# -.net
KiCad netlist of a schematic drawn in Altium Designer
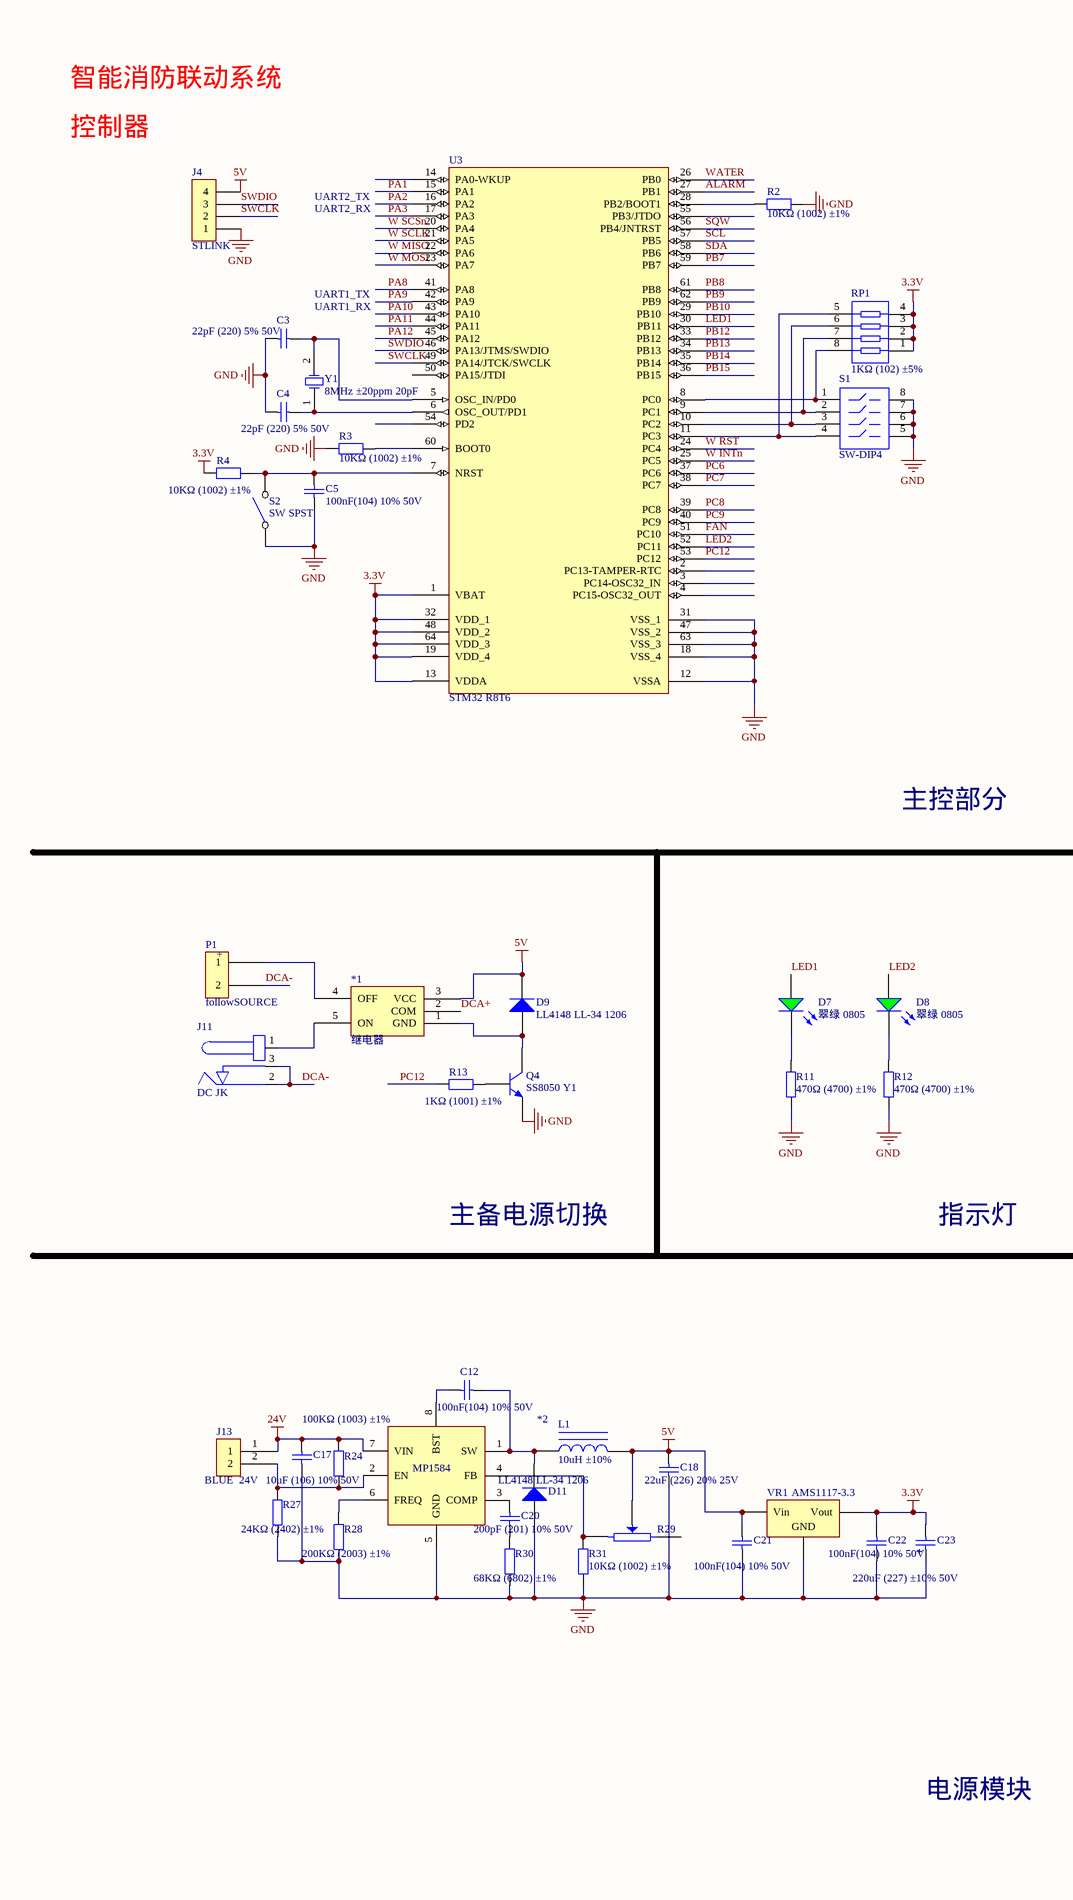
[diagram p0: 控制器最终图-论文用.SchDoc, left]
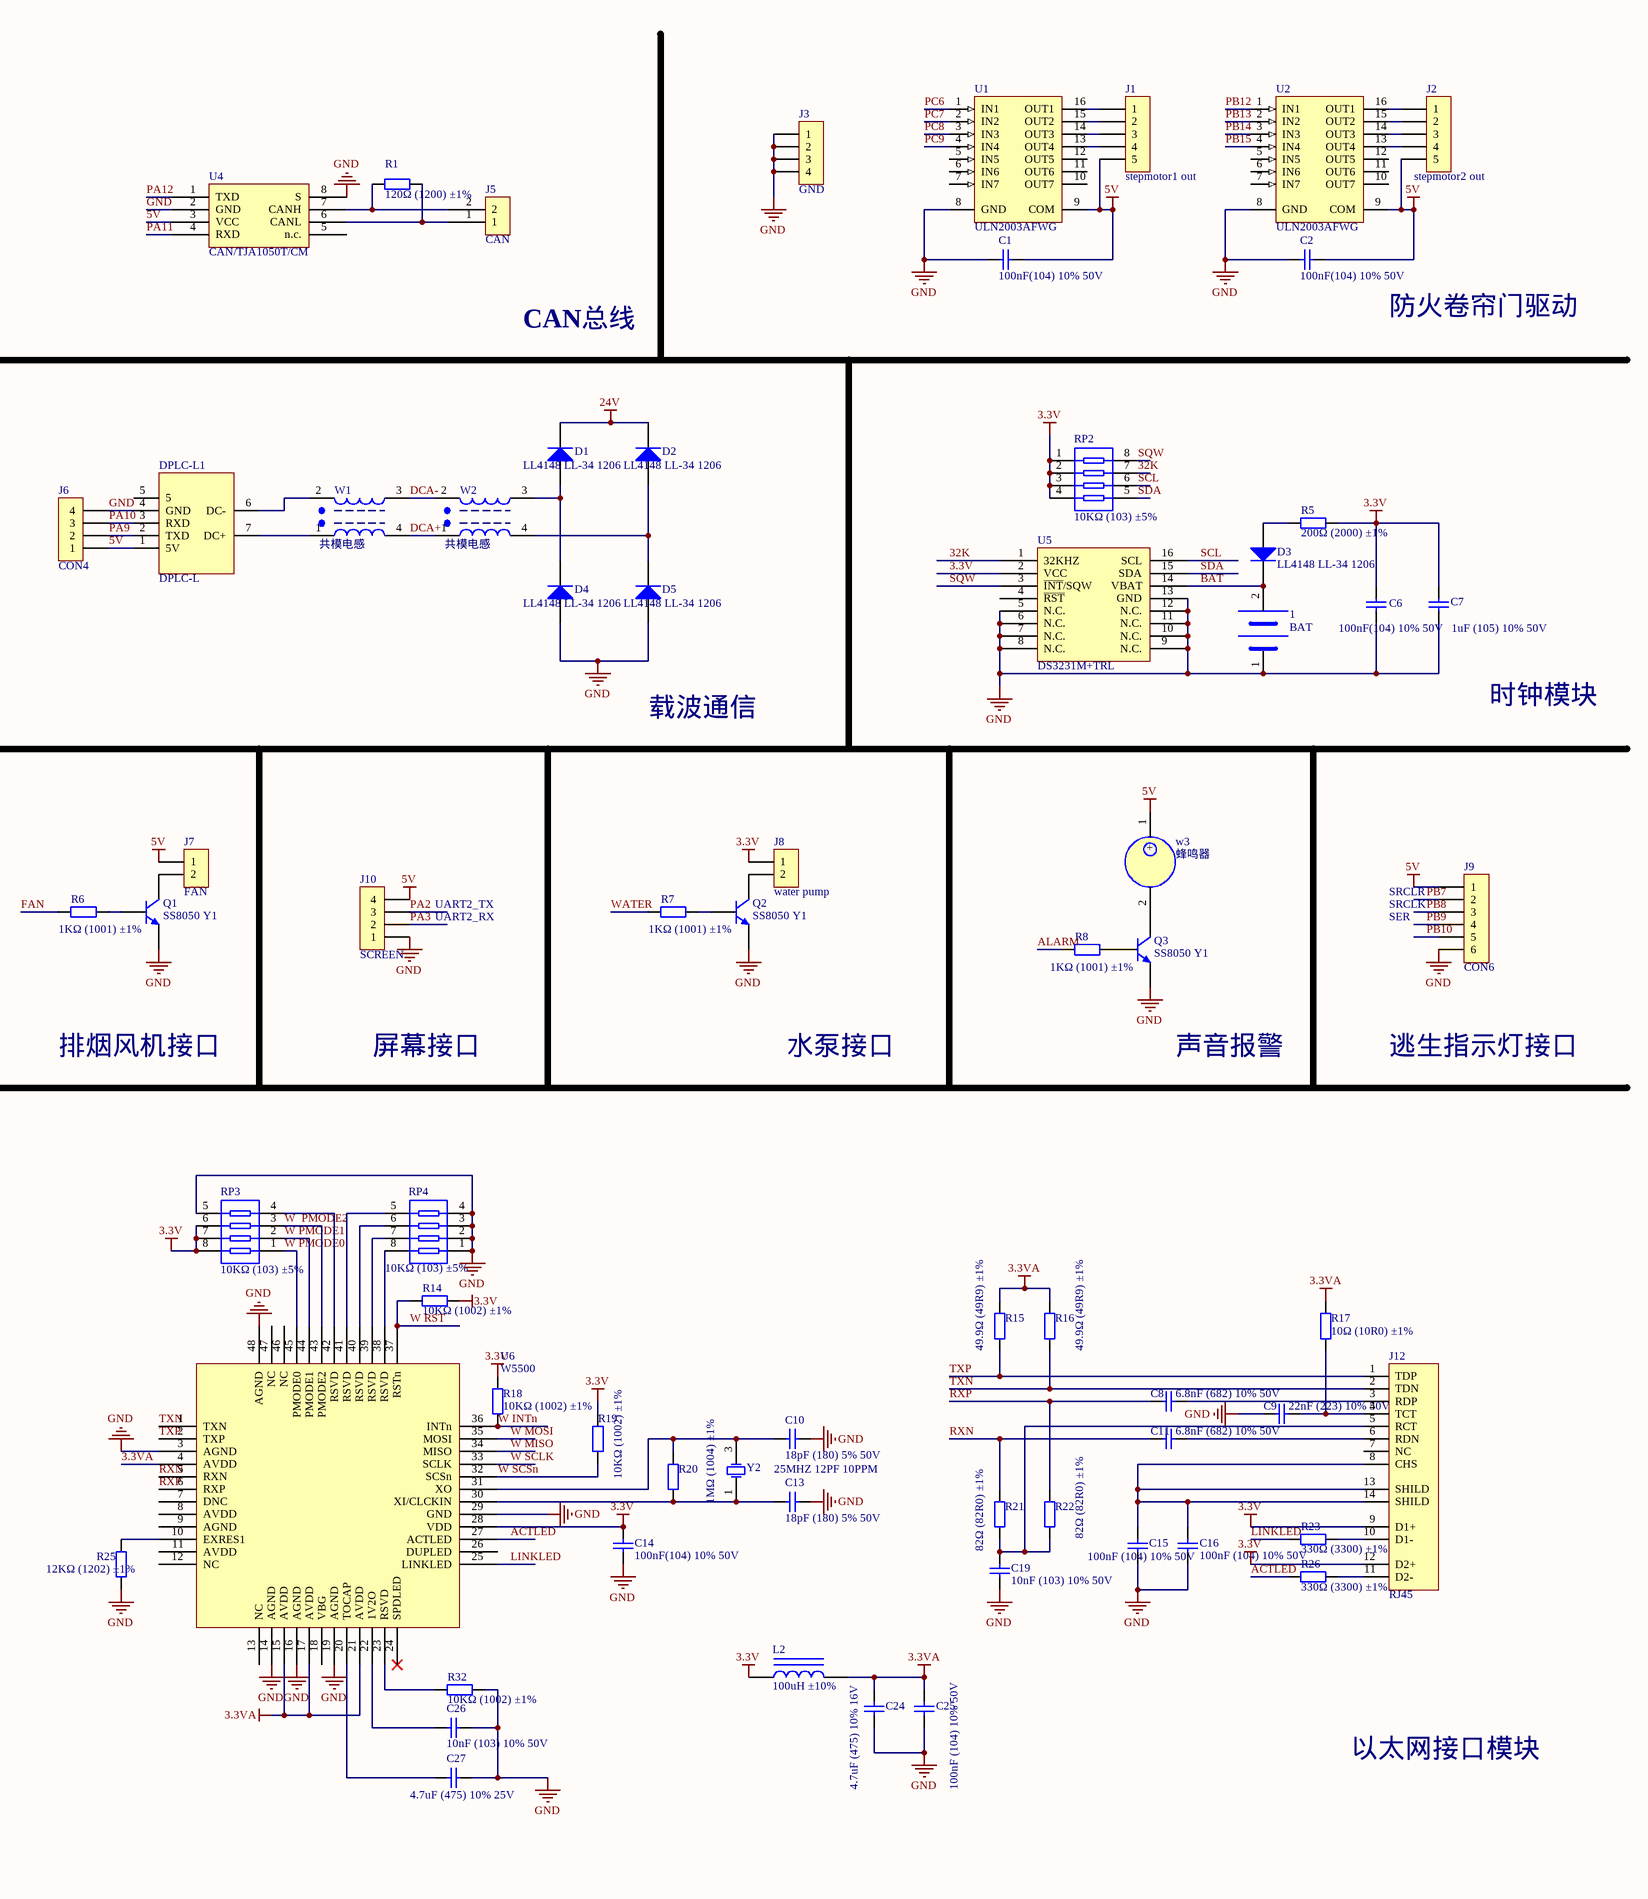
[diagram p1: 控制器最终图-论文用.SchDoc, right]

(export (version "E")
  (design (tool "Eeschema 10.0.6"))
  (components
    (comp (ref "*1") (value "继电器") (footprint "RLY-964") (libsource (lib "毕设原理图封装库") (part "继电器")))
    (comp (ref "*2") (value "MP1584") (libsource (lib "毕设原理图封装库") (part "MP1584")))
    (comp (ref "1") (value "BAT") (footprint "BAT") (libsource (lib "毕设原理图封装库") (part "BAT")))
    (comp (ref "C1")
      (value "100nF(104) 10% 50V")
      (footprint "LC-0805_C")
      (description "贴片电容")
      (libsource (lib "Miscellaneous Devices LC") (part "0805 100nF(104) 10% 50V"))
    )
    (comp (ref "C2")
      (value "100nF(104) 10% 50V")
      (footprint "LC-0805_C")
      (description "贴片电容")
      (libsource (lib "Miscellaneous Devices LC") (part "0805 100nF(104) 10% 50V"))
    )
    (comp (ref "C3")
      (value "22pF (220) 5% 50V")
      (footprint "LC-0805_C")
      (description "贴片电容")
      (libsource (lib "Miscellaneous Devices LC") (part "0805 22pF (220) 5% 50V"))
    )
    (comp (ref "C4")
      (value "22pF (220) 5% 50V")
      (footprint "LC-0805_C")
      (description "贴片电容")
      (libsource (lib "Miscellaneous Devices LC") (part "0805 22pF (220) 5% 50V"))
    )
    (comp (ref "C5")
      (value "100nF(104) 10% 50V")
      (footprint "LC-0805_C")
      (description "贴片电容")
      (libsource (lib "Miscellaneous Devices LC") (part "0805 100nF(104) 10% 50V"))
    )
    (comp (ref "C6")
      (value "100nF(104) 10% 50V")
      (footprint "LC-0805_C")
      (description "贴片电容")
      (libsource (lib "Miscellaneous Devices LC") (part "0805 100nF(104) 10% 50V"))
    )
    (comp (ref "C7")
      (value "1uF (105) 10% 50V")
      (footprint "LC-0805_C")
      (description "贴片电容")
      (libsource (lib "Miscellaneous Devices LC") (part "0805 1uF (105) 10% 50V"))
    )
    (comp (ref "C8")
      (value "6.8nF (682) 10% 50V")
      (footprint "LC-0603_C")
      (description "贴片电容")
      (libsource (lib "Miscellaneous Devices LC") (part "0603 6.8nF (682) 10% 50V"))
    )
    (comp (ref "C9")
      (value "22nF (223) 10% 50V")
      (footprint "LC-0603_C")
      (description "贴片电容")
      (libsource (lib "Miscellaneous Devices LC") (part "0603 22nF (223) 10% 50V"))
    )
    (comp (ref "C10")
      (value "18pF (180) 5% 50V")
      (footprint "LC-0805_C")
      (description "贴片电容")
      (libsource (lib "Miscellaneous Devices LC") (part "0805 18pF (180) 5% 50V"))
    )
    (comp (ref "C11")
      (value "6.8nF (682) 10% 50V")
      (footprint "LC-0603_C")
      (description "贴片电容")
      (libsource (lib "Miscellaneous Devices LC") (part "0603 6.8nF (682) 10% 50V"))
    )
    (comp (ref "C12")
      (value "100nF(104) 10% 50V")
      (footprint "LC-0805_C")
      (description "贴片电容")
      (libsource (lib "Miscellaneous Devices LC") (part "0805 100nF(104) 10% 50V"))
    )
    (comp (ref "C13")
      (value "18pF (180) 5% 50V")
      (footprint "LC-0805_C")
      (description "贴片电容")
      (libsource (lib "Miscellaneous Devices LC") (part "0805 18pF (180) 5% 50V"))
    )
    (comp (ref "C14")
      (value "100nF(104) 10% 50V")
      (footprint "LC-0805_C")
      (description "贴片电容")
      (libsource (lib "Miscellaneous Devices LC") (part "0805 100nF(104) 10% 50V"))
    )
    (comp (ref "C15")
      (value "100nF (104) 10% 50V")
      (footprint "LC-0603_C")
      (description "贴片电容")
      (libsource (lib "Miscellaneous Devices LC") (part "0603 100nF (104) 10% 50V"))
    )
    (comp (ref "C16")
      (value "100nF (104) 10% 50V")
      (footprint "LC-0603_C")
      (description "贴片电容")
      (libsource (lib "Miscellaneous Devices LC") (part "0603 100nF (104) 10% 50V"))
    )
    (comp (ref "C17")
      (value "10uF (106) 10% 50V")
      (footprint "LC-1206_C")
      (description "贴片电容")
      (libsource (lib "Miscellaneous Devices LC") (part "1206 10uF (106) 10% 50V"))
    )
    (comp (ref "C18")
      (value "22uF (226) 20% 25V")
      (footprint "LC-0805_C")
      (description "贴片电容")
      (libsource (lib "Miscellaneous Devices LC") (part "0805 22uF (226) 20% 25V"))
    )
    (comp (ref "C19")
      (value "10nF (103) 10% 50V")
      (footprint "LC-0603_C")
      (description "贴片电容")
      (libsource (lib "Miscellaneous Devices LC") (part "0603 10nF (103) 10% 50V"))
    )
    (comp (ref "C20")
      (value "200pF (201) 10% 50V")
      (footprint "LC-0805_C")
      (description "贴片电容")
      (libsource (lib "Miscellaneous Devices LC") (part "0805 200pF (201) 10% 50V"))
    )
    (comp (ref "C21")
      (value "100nF(104) 10% 50V")
      (footprint "LC-0805_C")
      (description "贴片电容")
      (libsource (lib "Miscellaneous Devices LC") (part "0805 100nF(104) 10% 50V"))
    )
    (comp (ref "C22")
      (value "100nF(104) 10% 50V")
      (footprint "LC-0805_C")
      (description "贴片电容")
      (libsource (lib "Miscellaneous Devices LC") (part "0805 100nF(104) 10% 50V"))
    )
    (comp (ref "C23")
      (value "220uF (227) ±10% 50V")
      (footprint "LC-CASE-B_3528")
      (description "钽电容")
      (libsource (lib "Miscellaneous Devices LC") (part "3528 100uF (107) 10% 6.3V"))
    )
    (comp (ref "C24")
      (value "4.7uF (475) 10% 16V")
      (footprint "LC-0603_C")
      (description "贴片电容")
      (libsource (lib "Miscellaneous Devices LC") (part "0603 4.7uF (475) 10% 16V"))
    )
    (comp (ref "C25")
      (value "100nF (104) 10% 50V")
      (footprint "LC-0603_C")
      (description "贴片电容")
      (libsource (lib "Miscellaneous Devices LC") (part "0603 100nF (104) 10% 50V"))
    )
    (comp (ref "C26")
      (value "10nF (103) 10% 50V")
      (footprint "LC-0805_C")
      (description "贴片电容")
      (libsource (lib "Miscellaneous Devices LC") (part "0805 10nF (103) 10% 50V"))
    )
    (comp (ref "C27")
      (value "4.7uF (475) 10% 25V")
      (footprint "LC-0805_C")
      (description "贴片电容")
      (libsource (lib "Miscellaneous Devices LC") (part "0805 4.7uF (475) 10% 25V"))
    )
    (comp (ref "D1")
      (value "LL4148 LL-34 1206")
      (footprint "LC-LL-34")
      (description "开关二极管")
      (libsource (lib "Miscellaneous Devices LC") (part "LL-34 LL4148 LL-34 1206"))
    )
    (comp (ref "D2")
      (value "LL4148 LL-34 1206")
      (footprint "LC-LL-34")
      (description "开关二极管")
      (libsource (lib "Miscellaneous Devices LC") (part "LL-34 LL4148 LL-34 1206"))
    )
    (comp (ref "D3")
      (value "LL4148 LL-34 1206")
      (footprint "LC-LL-34")
      (description "开关二极管")
      (libsource (lib "Miscellaneous Devices LC") (part "LL-34 LL4148 LL-34 1206"))
    )
    (comp (ref "D4")
      (value "LL4148 LL-34 1206")
      (footprint "LC-LL-34")
      (description "开关二极管")
      (libsource (lib "Miscellaneous Devices LC") (part "LL-34 LL4148 LL-34 1206"))
    )
    (comp (ref "D5")
      (value "LL4148 LL-34 1206")
      (footprint "LC-LL-34")
      (description "开关二极管")
      (libsource (lib "Miscellaneous Devices LC") (part "LL-34 LL4148 LL-34 1206"))
    )
    (comp (ref "D7")
      (value "翠绿 0805")
      (footprint "LC-0805_LED_S1")
      (description "发光二极管")
      (libsource (lib "Miscellaneous Devices LC") (part "0805 翠绿"))
    )
    (comp (ref "D8")
      (value "翠绿 0805")
      (footprint "LC-0805_LED_S1")
      (description "发光二极管")
      (libsource (lib "Miscellaneous Devices LC") (part "0805 翠绿"))
    )
    (comp (ref "D9")
      (value "LL4148 LL-34 1206")
      (footprint "LC-LL-34")
      (description "开关二极管")
      (libsource (lib "Miscellaneous Devices LC") (part "LL-34 LL4148 LL-34 1206"))
    )
    (comp (ref "D11")
      (value "LL4148 LL-34 1206")
      (footprint "LC-LL-34")
      (description "开关二极管")
      (libsource (lib "Miscellaneous Devices LC") (part "LL-34 LL4148 LL-34 1206"))
    )
    (comp (ref "DPLC-L1") (value "DPLC-L") (footprint "DPLC-L") (libsource (lib "毕设原理图封装库") (part "DPLC-L")))
    (comp (ref "J1") (value "stepmotor1 out") (footprint "防反插乘5") (libsource (lib "原理图封装库") (part "CON5")))
    (comp (ref "J2") (value "stepmotor2 out") (footprint "防反插乘5") (libsource (lib "原理图封装库") (part "CON5")))
    (comp (ref "J3") (value "GND") (footprint "SIP4") (libsource (lib "") (part "CON4_1")))
    (comp (ref "J4") (value "STLINK") (footprint "SIP4") (libsource (lib "毕设原理图封装库") (part "CON4")))
    (comp (ref "J5") (value "CAN") (footprint "蓝端子") (libsource (lib "") (part "蓝端子_1")))
    (comp (ref "J6") (value "CON4") (footprint "SIP4") (libsource (lib "毕设原理图封装库") (part "CON4")))
    (comp (ref "J7") (value "FAN") (footprint "SIP2") (libsource (lib "原理图封装库") (part "CON2")))
    (comp (ref "J8") (value "water pump") (footprint "SIP2") (libsource (lib "原理图封装库") (part "CON2")))
    (comp (ref "J9") (value "CON6") (footprint "SIP6") (libsource (lib "毕设原理图封装库") (part "CON6")))
    (comp (ref "J10") (value "SCREEN") (footprint "SIP4") (libsource (lib "毕设原理图封装库") (part "CON4")))
    (comp (ref "J11") (value "DC JK") (footprint "DC") (libsource (lib "Backup of 耳机座") (part "DC JK")))
    (comp (ref "J12") (value "RJ45") (footprint "RJ-45_GBE") (libsource (lib "毕设原理图封装库") (part "RJ45")))
    (comp (ref "J13") (value "BLUE  24V") (footprint "蓝端子") (libsource (lib "") (part "蓝端子_2")))
    (comp (ref "L1")
      (value "10uH ±10%")
      (footprint "LC-0805_L")
      (description "贴片电感")
      (libsource (lib "Miscellaneous Devices LC") (part "0805 10uH 10%"))
    )
    (comp (ref "L2")
      (value "100uH ±10%")
      (footprint "LC-0805_L")
      (description "贴片电感")
      (libsource (lib "Miscellaneous Devices LC") (part "0805 100uH 10%"))
    )
    (comp (ref "P1") (value "followSOURCE") (footprint "蓝端子") (libsource (lib "毕设原理图封装库") (part "蓝端子")))
    (comp (ref "Q1")
      (value "SS8050 Y1")
      (footprint "LC-SOT-23(SOT-23-3)")
      (description "三极管")
      (libsource (lib "Miscellaneous Devices LC") (part "SOT-23 SS8050 Y1"))
    )
    (comp (ref "Q2")
      (value "SS8050 Y1")
      (footprint "LC-SOT-23(SOT-23-3)")
      (description "三极管")
      (libsource (lib "Miscellaneous Devices LC") (part "SOT-23 SS8050 Y1"))
    )
    (comp (ref "Q3")
      (value "SS8050 Y1")
      (footprint "LC-SOT-23(SOT-23-3)")
      (description "三极管")
      (libsource (lib "Miscellaneous Devices LC") (part "SOT-23 SS8050 Y1"))
    )
    (comp (ref "Q4")
      (value "SS8050 Y1")
      (footprint "LC-SOT-23(SOT-23-3)")
      (description "三极管")
      (libsource (lib "Miscellaneous Devices LC") (part "SOT-23 SS8050 Y1"))
    )
    (comp (ref "R1")
      (value "120Ω (1200) ±1%")
      (footprint "LC-0805_R")
      (description "贴片电阻")
      (libsource (lib "Miscellaneous Devices LC") (part "0805 120Ω (1200) 1%"))
    )
    (comp (ref "R2")
      (value "10KΩ (1002) ±1%")
      (footprint "LC-0805_R")
      (description "贴片电阻")
      (libsource (lib "Miscellaneous Devices LC") (part "0805 10KΩ (1002) 1%"))
    )
    (comp (ref "R3")
      (value "10KΩ (1002) ±1%")
      (footprint "LC-0805_R")
      (description "贴片电阻")
      (libsource (lib "Miscellaneous Devices LC") (part "0805 10KΩ (1002) 1%"))
    )
    (comp (ref "R4")
      (value "10KΩ (1002) ±1%")
      (footprint "LC-0805_R")
      (description "贴片电阻")
      (libsource (lib "Miscellaneous Devices LC") (part "0805 10KΩ (1002) 1%"))
    )
    (comp (ref "R5")
      (value "200Ω (2000) ±1%")
      (footprint "LC-0805_R")
      (description "贴片电阻")
      (libsource (lib "Miscellaneous Devices LC") (part "0805 200Ω (2000) 1%"))
    )
    (comp (ref "R6")
      (value "1KΩ (1001) ±1%")
      (footprint "LC-0805_R")
      (description "贴片电阻")
      (libsource (lib "Miscellaneous Devices LC") (part "0805 1KΩ (1001) 1%"))
    )
    (comp (ref "R7")
      (value "1KΩ (1001) ±1%")
      (footprint "LC-0805_R")
      (description "贴片电阻")
      (libsource (lib "Miscellaneous Devices LC") (part "0805 1KΩ (1001) 1%"))
    )
    (comp (ref "R8")
      (value "1KΩ (1001) ±1%")
      (footprint "LC-0805_R")
      (description "贴片电阻")
      (libsource (lib "Miscellaneous Devices LC") (part "0805 1KΩ (1001) 1%"))
    )
    (comp (ref "R11")
      (value "470Ω (4700) ±1%")
      (footprint "LC-0805_R")
      (description "贴片电阻")
      (libsource (lib "Miscellaneous Devices LC") (part "0805 470Ω (4700) 1%"))
    )
    (comp (ref "R12")
      (value "470Ω (4700) ±1%")
      (footprint "LC-0805_R")
      (description "贴片电阻")
      (libsource (lib "Miscellaneous Devices LC") (part "0805 470Ω (4700) 1%"))
    )
    (comp (ref "R13")
      (value "1KΩ (1001) ±1%")
      (footprint "LC-0805_R")
      (description "贴片电阻")
      (libsource (lib "Miscellaneous Devices LC") (part "0805 1KΩ (1001) 1%"))
    )
    (comp (ref "R14")
      (value "10KΩ (1002) ±1%")
      (footprint "LC-0805_R")
      (description "贴片电阻")
      (libsource (lib "Miscellaneous Devices LC") (part "0805 10KΩ (1002) 1%"))
    )
    (comp (ref "R15")
      (value "49.9Ω (49R9) ±1%")
      (footprint "LC-0603_R")
      (description "贴片电阻")
      (libsource (lib "Miscellaneous Devices LC") (part "0603 49.9Ω (49R9) 1%"))
    )
    (comp (ref "R16")
      (value "49.9Ω (49R9) ±1%")
      (footprint "LC-0603_R")
      (description "贴片电阻")
      (libsource (lib "Miscellaneous Devices LC") (part "0603 49.9Ω (49R9) 1%"))
    )
    (comp (ref "R17")
      (value "10Ω (10R0) ±1%")
      (footprint "LC-0805_R")
      (description "贴片电阻")
      (libsource (lib "Miscellaneous Devices LC") (part "0805 10Ω (10R0) 1%"))
    )
    (comp (ref "R18")
      (value "10KΩ (1002) ±1%")
      (footprint "LC-0805_R")
      (description "贴片电阻")
      (libsource (lib "") (part "0805 10KΩ (1002) 1%_1"))
    )
    (comp (ref "R19")
      (value "10KΩ (1002) ±1%")
      (footprint "LC-0805_R")
      (description "贴片电阻")
      (libsource (lib "") (part "0805 10KΩ (1002) 1%_1"))
    )
    (comp (ref "R20")
      (value "1MΩ (1004) ±1%")
      (footprint "LC-0805_R")
      (description "贴片电阻")
      (libsource (lib "Miscellaneous Devices LC") (part "0805 1MΩ (1004) 1%"))
    )
    (comp (ref "R21")
      (value "82Ω (82R0) ±1%")
      (footprint "LC-0603_R")
      (description "贴片电阻")
      (libsource (lib "Miscellaneous Devices LC") (part "0603 82Ω (82R0) 1%"))
    )
    (comp (ref "R22")
      (value "82Ω (82R0) ±1%")
      (footprint "LC-0603_R")
      (description "贴片电阻")
      (libsource (lib "Miscellaneous Devices LC") (part "0603 82Ω (82R0) 1%"))
    )
    (comp (ref "R23")
      (value "330Ω (3300) ±1%")
      (footprint "LC-0603_R")
      (description "贴片电阻")
      (libsource (lib "Miscellaneous Devices LC") (part "0603 330Ω (3300) 1%"))
    )
    (comp (ref "R24")
      (value "100KΩ (1003) ±1%")
      (footprint "LC-0805_R")
      (description "贴片电阻")
      (libsource (lib "Miscellaneous Devices LC") (part "0805 100KΩ (1003) 1%"))
    )
    (comp (ref "R25")
      (value "12KΩ (1202) ±1%")
      (footprint "LC-0805_R")
      (description "贴片电阻")
      (libsource (lib "Miscellaneous Devices LC") (part "0805 12KΩ (1202) 1%"))
    )
    (comp (ref "R26")
      (value "330Ω (3300) ±1%")
      (footprint "LC-0603_R")
      (description "贴片电阻")
      (libsource (lib "Miscellaneous Devices LC") (part "0603 330Ω (3300) 1%"))
    )
    (comp (ref "R27")
      (value "24KΩ (2402) ±1%")
      (footprint "LC-0805_R")
      (description "贴片电阻")
      (libsource (lib "Miscellaneous Devices LC") (part "0805 24KΩ (2402) 1%"))
    )
    (comp (ref "R28")
      (value "200KΩ (2003) ±1%")
      (footprint "LC-0805_R")
      (description "贴片电阻")
      (libsource (lib "Miscellaneous Devices LC") (part "0805 200KΩ (2003) 1%"))
    )
    (comp (ref "R29") (value "2") (description "滑变2") (libsource (lib "原理图封装库") (part "POT2")))
    (comp (ref "R30")
      (value "68KΩ (6802) ±1%")
      (footprint "LC-0805_R")
      (description "贴片电阻")
      (libsource (lib "Miscellaneous Devices LC") (part "0805 68KΩ (6802) 1%"))
    )
    (comp (ref "R31")
      (value "10KΩ (1002) ±1%")
      (footprint "LC-0805_R")
      (description "贴片电阻")
      (libsource (lib "") (part "0805 10KΩ (1002) 1%_1"))
    )
    (comp (ref "R32")
      (value "10KΩ (1002) ±1%")
      (footprint "LC-0805_R")
      (description "贴片电阻")
      (libsource (lib "Miscellaneous Devices LC") (part "0805 10KΩ (1002) 1%"))
    )
    (comp (ref "RP1")
      (value "1KΩ (102) ±5%")
      (footprint "LC-0603_Rx4")
      (description "贴片排阻")
      (libsource (lib "Miscellaneous Devices LC") (part "0603*4  1KΩ (102) 5%"))
    )
    (comp (ref "RP2")
      (value "10KΩ (103) ±5%")
      (footprint "LC-0603_Rx4")
      (description "贴片排阻")
      (libsource (lib "Miscellaneous Devices LC") (part "0603*4  10KΩ (103) 5%"))
    )
    (comp (ref "RP3")
      (value "10KΩ (103) ±5%")
      (footprint "LC-0603_Rx4")
      (description "贴片排阻")
      (libsource (lib "Miscellaneous Devices LC") (part "0603*4  10KΩ (103) 5%"))
    )
    (comp (ref "RP4")
      (value "10KΩ (103) ±5%")
      (footprint "LC-0603_Rx4")
      (description "贴片排阻")
      (libsource (lib "Miscellaneous Devices LC") (part "0603*4  10KΩ (103) 5%"))
    )
    (comp (ref "S1")
      (value "SW-DIP4")
      (footprint "4位拨码开关")
      (description "4位拨码开关")
      (libsource (lib "毕设原理图封装库") (part "SW-DIP4"))
    )
    (comp (ref "S2")
      (value "SW SPST")
      (footprint "单片机小按键")
      (description "单刀单掷开关")
      (libsource (lib "毕设原理图封装库") (part "SW SPST"))
    )
    (comp (ref "U1")
      (value "ULN2003AFWG")
      (footprint "LC-SOIC-16_150mil")
      (description "大电流驱动")
      (libsource (lib "Miscellaneous Devices LC") (part "ULN2003AFWG"))
    )
    (comp (ref "U2")
      (value "ULN2003AFWG")
      (footprint "LC-SOIC-16_150mil")
      (description "大电流驱动")
      (libsource (lib "Miscellaneous Devices LC") (part "ULN2003AFWG"))
    )
    (comp (ref "U3")
      (value "STM32 R8T6")
      (footprint "LC-LQFP-64_10x10x05P")
      (libsource (lib "毕设原理图封装库") (part "STM32 R8T6"))
    )
    (comp (ref "U4")
      (value "CAN/TJA1050T/CM")
      (footprint "LC-SOIC-8_150mil")
      (description "CAN")
      (libsource (lib "Miscellaneous Devices LC") (part "CAN/TJA1050T/CM"))
    )
    (comp (ref "U5")
      (value "DS3231M+TRL")
      (footprint "LC-SOIC-16_300mil")
      (description "实时时钟")
      (libsource (lib "Miscellaneous Devices LC") (part "DS3231M+TRL"))
    )
    (comp (ref "U6")
      (value "W5500")
      (footprint "LC-LQFP-48_7x7x05P")
      (description "以太网")
      (libsource (lib "Miscellaneous Devices LC") (part "W5500"))
    )
    (comp (ref "VR1")
      (value "AMS1117-3.3")
      (footprint "LC-SOT-223")
      (description "低压差线性稳压(LDO)")
      (libsource (lib "Miscellaneous Devices LC") (part "SOT-223 AMS1117-3.3"))
    )
    (comp (ref "W1") (value "共模电感") (footprint "共模电感") (libsource (lib "毕设原理图封装库") (part "共模电感")))
    (comp (ref "W2") (value "共模电感") (footprint "共模电感") (libsource (lib "毕设原理图封装库") (part "共模电感")))
    (comp (ref "w3") (value "蜂鸣器") (footprint "蜂鸣器") (libsource (lib "毕设原理图封装库") (part "蜂鸣器")))
    (comp (ref "Y1")
      (value "8MHz ±20ppm 20pF")
      (footprint "LC-SMD-5032_2P")
      (description "贴片晶振")
      (libsource (lib "Miscellaneous Devices LC") (part "SMD-5032_2P 8MHz 20ppm 20pF"))
    )
    (comp (ref "Y2")
      (value "25MHZ 12PF 10PPM")
      (footprint "LC-SMD-3225_4P")
      (description "贴片晶振")
      (libsource (lib "Miscellaneous Devices LC") (part "SMD-3225_4P  25MHZ 12PF 10PPM"))
    )
  )
  (nets
    (net (code "1") (name "/32K") (class "Default")
      (node (ref "RP2") (pin "7") (pinfunction "7_7") (pintype "passive"))
      (node (ref "U5") (pin "1") (pinfunction "32KHZ_1") (pintype "passive"))
    )
    (net (code "2") (name "/ACTLED") (class "Default")
      (node (ref "R26") (pin "1") (pinfunction "1_1") (pintype "passive"))
      (node (ref "U6") (pin "27") (pinfunction "ACTLED_27") (pintype "passive"))
    )
    (net (code "3") (name "/ALARM") (class "Default")
      (node (ref "R8") (pin "1") (pinfunction "1_1") (pintype "passive"))
      (node (ref "U3") (pin "27") (pinfunction "PB1_27") (pintype "bidirectional"))
    )
    (net (code "4") (name "/BAT") (class "Default")
      (node (ref "1") (pin "2") (pinfunction "2_2") (pintype "passive"))
      (node (ref "D3") (pin "2") (pinfunction "K_2") (pintype "passive"))
      (node (ref "U5") (pin "14") (pinfunction "VBAT_14") (pintype "passive"))
    )
    (net (code "5") (name "/DCA+") (class "Default")
      (node (ref "*1") (pin "2") (pinfunction "COM_2") (pintype "passive"))
      (node (ref "W1") (pin "4") (pinfunction "4_4") (pintype "passive"))
      (node (ref "W2") (pin "1") (pinfunction "1_1") (pintype "passive"))
    )
    (net (code "6") (name "/DCA-") (class "Default")
      (node (ref "J11") (pin "2") (pinfunction "GND_2") (pintype "passive"))
      (node (ref "J11") (pin "3") (pinfunction "GND_3") (pintype "passive"))
      (node (ref "P1") (pin "2") (pinfunction "2_2") (pintype "passive"))
      (node (ref "W1") (pin "3") (pinfunction "3_3") (pintype "passive"))
      (node (ref "W2") (pin "2") (pinfunction "2_2") (pintype "passive"))
    )
    (net (code "7") (name "/FAN") (class "Default")
      (node (ref "R6") (pin "1") (pinfunction "1_1") (pintype "passive"))
      (node (ref "U3") (pin "51") (pinfunction "PC10_51") (pintype "bidirectional"))
    )
    (net (code "8") (name "/LED1") (class "Default")
      (node (ref "D7") (pin "A") (pinfunction "A_A") (pintype "passive"))
      (node (ref "U3") (pin "30") (pinfunction "PB11_30") (pintype "bidirectional"))
    )
    (net (code "9") (name "/LED2") (class "Default")
      (node (ref "D8") (pin "A") (pinfunction "A_A") (pintype "passive"))
      (node (ref "U3") (pin "52") (pinfunction "PC11_52") (pintype "bidirectional"))
    )
    (net (code "10") (name "/LINKLED") (class "Default")
      (node (ref "R23") (pin "1") (pinfunction "1_1") (pintype "passive"))
      (node (ref "U6") (pin "25") (pinfunction "LINKLED_25") (pintype "passive"))
    )
    (net (code "11") (name "/PA1") (class "Default")
      (node (ref "U3") (pin "15") (pinfunction "PA1_15") (pintype "bidirectional"))
    )
    (net (code "12") (name "/PA2") (class "Default")
      (node (ref "J10") (pin "3") (pinfunction "3_3") (pintype "passive"))
      (node (ref "U3") (pin "16") (pinfunction "PA2_16") (pintype "bidirectional"))
    )
    (net (code "13") (name "/PA3") (class "Default")
      (node (ref "J10") (pin "2") (pinfunction "2_2") (pintype "passive"))
      (node (ref "U3") (pin "17") (pinfunction "PA3_17") (pintype "bidirectional"))
    )
    (net (code "14") (name "/PA8") (class "Default")
      (node (ref "U3") (pin "41") (pinfunction "PA8_41") (pintype "bidirectional"))
    )
    (net (code "15") (name "/PA9") (class "Default")
      (node (ref "DPLC-L1") (pin "2") (pinfunction "TXD_2") (pintype "passive"))
      (node (ref "J6") (pin "2") (pinfunction "2_2") (pintype "passive"))
      (node (ref "U3") (pin "42") (pinfunction "PA9_42") (pintype "bidirectional"))
    )
    (net (code "16") (name "/PA10") (class "Default")
      (node (ref "DPLC-L1") (pin "3") (pinfunction "RXD_3") (pintype "passive"))
      (node (ref "J6") (pin "3") (pinfunction "3_3") (pintype "passive"))
      (node (ref "U3") (pin "43") (pinfunction "PA10_43") (pintype "bidirectional"))
    )
    (net (code "17") (name "/PA11") (class "Default")
      (node (ref "U3") (pin "44") (pinfunction "PA11_44") (pintype "bidirectional"))
      (node (ref "U4") (pin "4") (pinfunction "RXD_4") (pintype "passive"))
    )
    (net (code "18") (name "/PA12") (class "Default")
      (node (ref "U3") (pin "45") (pinfunction "PA12_45") (pintype "bidirectional"))
      (node (ref "U4") (pin "1") (pinfunction "TXD_1") (pintype "passive"))
    )
    (net (code "19") (name "/PB7") (class "Default")
      (node (ref "J9") (pin "2") (pinfunction "2_2") (pintype "passive"))
      (node (ref "U3") (pin "59") (pinfunction "PB7_59") (pintype "bidirectional"))
    )
    (net (code "20") (name "/PB8") (class "Default")
      (node (ref "J9") (pin "3") (pinfunction "3_3") (pintype "passive"))
      (node (ref "U3") (pin "61") (pinfunction "PB8_61") (pintype "bidirectional"))
    )
    (net (code "21") (name "/PB9") (class "Default")
      (node (ref "J9") (pin "4") (pinfunction "4_4") (pintype "passive"))
      (node (ref "U3") (pin "62") (pinfunction "PB9_62") (pintype "bidirectional"))
    )
    (net (code "22") (name "/PB10") (class "Default")
      (node (ref "J9") (pin "5") (pinfunction "5_5") (pintype "passive"))
      (node (ref "U3") (pin "29") (pinfunction "PB10_29") (pintype "bidirectional"))
    )
    (net (code "23") (name "/PB12") (class "Default")
      (node (ref "U2") (pin "1") (pinfunction "IN1_1") (pintype "input"))
      (node (ref "U3") (pin "33") (pinfunction "PB12_33") (pintype "bidirectional"))
    )
    (net (code "24") (name "/PB13") (class "Default")
      (node (ref "U2") (pin "2") (pinfunction "IN2_2") (pintype "input"))
      (node (ref "U3") (pin "34") (pinfunction "PB13_34") (pintype "bidirectional"))
    )
    (net (code "25") (name "/PB14") (class "Default")
      (node (ref "U2") (pin "3") (pinfunction "IN3_3") (pintype "input"))
      (node (ref "U3") (pin "35") (pinfunction "PB14_35") (pintype "bidirectional"))
    )
    (net (code "26") (name "/PB15") (class "Default")
      (node (ref "U2") (pin "4") (pinfunction "IN4_4") (pintype "input"))
      (node (ref "U3") (pin "36") (pinfunction "PB15_36") (pintype "bidirectional"))
    )
    (net (code "27") (name "/PC6") (class "Default")
      (node (ref "U1") (pin "1") (pinfunction "IN1_1") (pintype "input"))
      (node (ref "U3") (pin "37") (pinfunction "PC6_37") (pintype "bidirectional"))
    )
    (net (code "28") (name "/PC7") (class "Default")
      (node (ref "U1") (pin "2") (pinfunction "IN2_2") (pintype "input"))
      (node (ref "U3") (pin "38") (pinfunction "PC7_38") (pintype "bidirectional"))
    )
    (net (code "29") (name "/PC8") (class "Default")
      (node (ref "U1") (pin "3") (pinfunction "IN3_3") (pintype "input"))
      (node (ref "U3") (pin "39") (pinfunction "PC8_39") (pintype "bidirectional"))
    )
    (net (code "30") (name "/PC9") (class "Default")
      (node (ref "U1") (pin "4") (pinfunction "IN4_4") (pintype "input"))
      (node (ref "U3") (pin "40") (pinfunction "PC9_40") (pintype "bidirectional"))
    )
    (net (code "31") (name "/PC12") (class "Default")
      (node (ref "R13") (pin "1") (pinfunction "1_1") (pintype "passive"))
      (node (ref "U3") (pin "53") (pinfunction "PC12_53") (pintype "bidirectional"))
    )
    (net (code "32") (name "/RXN") (class "Default")
      (node (ref "C11") (pin "1") (pinfunction "1_1") (pintype "passive"))
      (node (ref "R21") (pin "2") (pinfunction "2_2") (pintype "passive"))
      (node (ref "U6") (pin "5") (pinfunction "RXN_5") (pintype "passive"))
    )
    (net (code "33") (name "/RXP") (class "Default")
      (node (ref "C8") (pin "1") (pinfunction "1_1") (pintype "passive"))
      (node (ref "R22") (pin "2") (pinfunction "2_2") (pintype "passive"))
      (node (ref "U6") (pin "6") (pinfunction "RXP_6") (pintype "passive"))
    )
    (net (code "34") (name "/SCL") (class "Default")
      (node (ref "RP2") (pin "6") (pinfunction "6_6") (pintype "passive"))
      (node (ref "U3") (pin "57") (pinfunction "PB5_57") (pintype "bidirectional"))
      (node (ref "U5") (pin "16") (pinfunction "SCL_16") (pintype "passive"))
    )
    (net (code "35") (name "/SDA") (class "Default")
      (node (ref "RP2") (pin "5") (pinfunction "5_5") (pintype "passive"))
      (node (ref "U3") (pin "58") (pinfunction "PB6_58") (pintype "bidirectional"))
      (node (ref "U5") (pin "15") (pinfunction "SDA_15") (pintype "passive"))
    )
    (net (code "36") (name "/SQW") (class "Default")
      (node (ref "RP2") (pin "8") (pinfunction "8_8") (pintype "passive"))
      (node (ref "U3") (pin "56") (pinfunction "PB4/JNTRST_56") (pintype "bidirectional"))
      (node (ref "U5") (pin "3") (pinfunction "~{INT}/SQW_3") (pintype "passive"))
    )
    (net (code "37") (name "/SWCLK") (class "Default")
      (node (ref "J4") (pin "2") (pinfunction "2_2") (pintype "passive"))
      (node (ref "U3") (pin "49") (pinfunction "PA14/JTCK/SWCLK_49") (pintype "bidirectional"))
    )
    (net (code "38") (name "/SWDIO") (class "Default")
      (node (ref "J4") (pin "3") (pinfunction "3_3") (pintype "passive"))
      (node (ref "U3") (pin "46") (pinfunction "PA13/JTMS/SWDIO_46") (pintype "bidirectional"))
    )
    (net (code "39") (name "/TXN") (class "Default")
      (node (ref "J12") (pin "2") (pinfunction "TDN_2") (pintype "passive"))
      (node (ref "R16") (pin "1") (pinfunction "1_1") (pintype "passive"))
      (node (ref "U6") (pin "1") (pinfunction "TXN_1") (pintype "passive"))
    )
    (net (code "40") (name "/TXP") (class "Default")
      (node (ref "J12") (pin "1") (pinfunction "TDP_1") (pintype "passive"))
      (node (ref "R15") (pin "1") (pinfunction "1_1") (pintype "passive"))
      (node (ref "U6") (pin "2") (pinfunction "TXP_2") (pintype "passive"))
    )
    (net (code "41") (name "/W  PMODE2") (class "Default")
      (node (ref "RP3") (pin "3") (pinfunction "3_3") (pintype "passive"))
      (node (ref "U6") (pin "43") (pinfunction "PMODE2_43") (pintype "passive"))
    )
    (net (code "42") (name "/W INTn") (class "Default")
      (node (ref "R18") (pin "1") (pinfunction "1_1") (pintype "passive"))
      (node (ref "U3") (pin "25") (pinfunction "PC5_25") (pintype "bidirectional"))
      (node (ref "U6") (pin "36") (pinfunction "INTn_36") (pintype "passive"))
    )
    (net (code "43") (name "/W MISO") (class "Default")
      (node (ref "U3") (pin "22") (pinfunction "PA6_22") (pintype "bidirectional"))
      (node (ref "U6") (pin "34") (pinfunction "MISO_34") (pintype "passive"))
    )
    (net (code "44") (name "/W MOSI") (class "Default")
      (node (ref "U3") (pin "23") (pinfunction "PA7_23") (pintype "bidirectional"))
      (node (ref "U6") (pin "35") (pinfunction "MOSI_35") (pintype "passive"))
    )
    (net (code "45") (name "/W PMODE0") (class "Default")
      (node (ref "RP3") (pin "1") (pinfunction "1_1") (pintype "passive"))
      (node (ref "U6") (pin "45") (pinfunction "PMODE0_45") (pintype "passive"))
    )
    (net (code "46") (name "/W PMODE1") (class "Default")
      (node (ref "RP3") (pin "2") (pinfunction "2_2") (pintype "passive"))
      (node (ref "U6") (pin "44") (pinfunction "PMODE1_44") (pintype "passive"))
    )
    (net (code "47") (name "/W RST") (class "Default")
      (node (ref "R14") (pin "1") (pinfunction "1_1") (pintype "passive"))
      (node (ref "U3") (pin "24") (pinfunction "PC4_24") (pintype "bidirectional"))
      (node (ref "U6") (pin "37") (pinfunction "RSTn_37") (pintype "passive"))
    )
    (net (code "48") (name "/W SCLK") (class "Default")
      (node (ref "U3") (pin "21") (pinfunction "PA5_21") (pintype "bidirectional"))
      (node (ref "U6") (pin "33") (pinfunction "SCLK_33") (pintype "passive"))
    )
    (net (code "49") (name "/W SCSn") (class "Default")
      (node (ref "R19") (pin "1") (pinfunction "1_1") (pintype "passive"))
      (node (ref "U3") (pin "20") (pinfunction "PA4_20") (pintype "bidirectional"))
      (node (ref "U6") (pin "32") (pinfunction "SCSn_32") (pintype "passive"))
    )
    (net (code "50") (name "/WATER") (class "Default")
      (node (ref "R7") (pin "1") (pinfunction "1_1") (pintype "passive"))
      (node (ref "U3") (pin "26") (pinfunction "PB0_26") (pintype "bidirectional"))
    )
    (net (code "51") (name "3.3V") (class "Default")
      (node (ref "C14") (pin "2") (pinfunction "2_2") (pintype "passive"))
      (node (ref "C22") (pin "1") (pinfunction "1_1") (pintype "passive"))
      (node (ref "C23") (pin "2") (pinfunction "2_2") (pintype "passive"))
      (node (ref "C6") (pin "2") (pinfunction "2_2") (pintype "passive"))
      (node (ref "C7") (pin "2") (pinfunction "2_2") (pintype "passive"))
      (node (ref "J12") (pin "12") (pinfunction "D2+_12") (pintype "passive"))
      (node (ref "J12") (pin "9") (pinfunction "D1+_9") (pintype "passive"))
      (node (ref "J8") (pin "1") (pinfunction "1_1") (pintype "passive"))
      (node (ref "L2") (pin "1") (pinfunction "1_1") (pintype "passive"))
      (node (ref "R14") (pin "2") (pinfunction "2_2") (pintype "passive"))
      (node (ref "R18") (pin "2") (pinfunction "2_2") (pintype "passive"))
      (node (ref "R19") (pin "2") (pinfunction "2_2") (pintype "passive"))
      (node (ref "R4") (pin "1") (pinfunction "1_1") (pintype "passive"))
      (node (ref "R5") (pin "1") (pinfunction "1_1") (pintype "passive"))
      (node (ref "RP1") (pin "1") (pinfunction "1_1") (pintype "passive"))
      (node (ref "RP1") (pin "2") (pinfunction "2_2") (pintype "passive"))
      (node (ref "RP1") (pin "3") (pinfunction "3_3") (pintype "passive"))
      (node (ref "RP1") (pin "4") (pinfunction "4_4") (pintype "passive"))
      (node (ref "RP2") (pin "1") (pinfunction "1_1") (pintype "passive"))
      (node (ref "RP2") (pin "2") (pinfunction "2_2") (pintype "passive"))
      (node (ref "RP2") (pin "3") (pinfunction "3_3") (pintype "passive"))
      (node (ref "RP2") (pin "4") (pinfunction "4_4") (pintype "passive"))
      (node (ref "RP3") (pin "6") (pinfunction "6_6") (pintype "passive"))
      (node (ref "RP3") (pin "7") (pinfunction "7_7") (pintype "passive"))
      (node (ref "RP3") (pin "8") (pinfunction "8_8") (pintype "passive"))
      (node (ref "U3") (pin "1") (pinfunction "VBAT_1") (pintype "power_in"))
      (node (ref "U3") (pin "13") (pinfunction "VDDA_13") (pintype "power_in"))
      (node (ref "U3") (pin "19") (pinfunction "VDD_4_19") (pintype "power_in"))
      (node (ref "U3") (pin "32") (pinfunction "VDD_1_32") (pintype "power_in"))
      (node (ref "U3") (pin "48") (pinfunction "VDD_2_48") (pintype "power_in"))
      (node (ref "U3") (pin "64") (pinfunction "VDD_3_64") (pintype "power_in"))
      (node (ref "U5") (pin "2") (pinfunction "VCC_2") (pintype "passive"))
      (node (ref "U6") (pin "28") (pinfunction "VDD_28") (pintype "passive"))
      (node (ref "VR1") (pin "2") (pinfunction "Vout_2") (pintype "passive"))
    )
    (net (code "52") (name "3.3VA") (class "Default")
      (node (ref "C24") (pin "2") (pinfunction "2_2") (pintype "passive"))
      (node (ref "C25") (pin "2") (pinfunction "2_2") (pintype "passive"))
      (node (ref "L2") (pin "2") (pinfunction "2_2") (pintype "passive"))
      (node (ref "R15") (pin "2") (pinfunction "2_2") (pintype "passive"))
      (node (ref "R16") (pin "2") (pinfunction "2_2") (pintype "passive"))
      (node (ref "R17") (pin "2") (pinfunction "2_2") (pintype "passive"))
      (node (ref "U6") (pin "15") (pinfunction "AVDD_15") (pintype "passive"))
      (node (ref "U6") (pin "17") (pinfunction "AVDD_17") (pintype "passive"))
      (node (ref "U6") (pin "21") (pinfunction "AVDD_21") (pintype "passive"))
      (node (ref "U6") (pin "4") (pinfunction "AVDD_4") (pintype "passive"))
    )
    (net (code "53") (name "5V") (class "Default")
      (node (ref "*1") (pin "3") (pinfunction "VCC_3") (pintype "passive"))
      (node (ref "C1") (pin "2") (pinfunction "2_2") (pintype "passive"))
      (node (ref "C18") (pin "2") (pinfunction "2_2") (pintype "passive"))
      (node (ref "C2") (pin "2") (pinfunction "2_2") (pintype "passive"))
      (node (ref "C21") (pin "2") (pinfunction "2_2") (pintype "passive"))
      (node (ref "D9") (pin "2") (pinfunction "K_2") (pintype "passive"))
      (node (ref "DPLC-L1") (pin "1") (pinfunction "5V_1") (pintype "passive"))
      (node (ref "J1") (pin "5") (pinfunction "5_5") (pintype "passive"))
      (node (ref "J10") (pin "4") (pinfunction "4_4") (pintype "passive"))
      (node (ref "J2") (pin "5") (pinfunction "5_5") (pintype "passive"))
      (node (ref "J4") (pin "4") (pinfunction "4_4") (pintype "passive"))
      (node (ref "J6") (pin "1") (pinfunction "1_1") (pintype "passive"))
      (node (ref "J7") (pin "1") (pinfunction "1_1") (pintype "passive"))
      (node (ref "J9") (pin "1") (pinfunction "1_1") (pintype "passive"))
      (node (ref "L1") (pin "2") (pinfunction "2_2") (pintype "passive"))
      (node (ref "R29") (pin "3") (pinfunction "W_3") (pintype "passive"))
      (node (ref "U1") (pin "9") (pinfunction "COM_9") (pintype "passive"))
      (node (ref "U2") (pin "9") (pinfunction "COM_9") (pintype "passive"))
      (node (ref "U4") (pin "3") (pinfunction "VCC_3") (pintype "passive"))
      (node (ref "VR1") (pin "3") (pinfunction "Vin_3") (pintype "passive"))
      (node (ref "w3") (pin "1") (pinfunction "+_1") (pintype "passive"))
    )
    (net (code "54") (name "24V") (class "Default")
      (node (ref "*2") (pin "7") (pinfunction "VIN_7") (pintype "passive"))
      (node (ref "C17") (pin "2") (pinfunction "2_2") (pintype "passive"))
      (node (ref "D1") (pin "2") (pinfunction "K_2") (pintype "passive"))
      (node (ref "D2") (pin "2") (pinfunction "K_2") (pintype "passive"))
      (node (ref "J13") (pin "1") (pinfunction "1_1") (pintype "passive"))
      (node (ref "R24") (pin "2") (pinfunction "2_2") (pintype "passive"))
    )
    (net (code "55") (name "GND") (class "Default")
      (node (ref "*2") (pin "5") (pinfunction "GND_5") (pintype "passive"))
      (node (ref "1") (pin "1") (pinfunction "1_1") (pintype "passive"))
      (node (ref "C1") (pin "1") (pinfunction "1_1") (pintype "passive"))
      (node (ref "C10") (pin "2") (pinfunction "2_2") (pintype "passive"))
      (node (ref "C13") (pin "2") (pinfunction "2_2") (pintype "passive"))
      (node (ref "C14") (pin "1") (pinfunction "1_1") (pintype "passive"))
      (node (ref "C15") (pin "1") (pinfunction "1_1") (pintype "passive"))
      (node (ref "C16") (pin "1") (pinfunction "1_1") (pintype "passive"))
      (node (ref "C17") (pin "1") (pinfunction "1_1") (pintype "passive"))
      (node (ref "C18") (pin "1") (pinfunction "1_1") (pintype "passive"))
      (node (ref "C19") (pin "1") (pinfunction "1_1") (pintype "passive"))
      (node (ref "C2") (pin "1") (pinfunction "1_1") (pintype "passive"))
      (node (ref "C21") (pin "1") (pinfunction "1_1") (pintype "passive"))
      (node (ref "C22") (pin "2") (pinfunction "2_2") (pintype "passive"))
      (node (ref "C23") (pin "1") (pinfunction "1_1") (pintype "passive"))
      (node (ref "C24") (pin "1") (pinfunction "1_1") (pintype "passive"))
      (node (ref "C25") (pin "1") (pinfunction "1_1") (pintype "passive"))
      (node (ref "C26") (pin "2") (pinfunction "2_2") (pintype "passive"))
      (node (ref "C27") (pin "2") (pinfunction "2_2") (pintype "passive"))
      (node (ref "C3") (pin "1") (pinfunction "1_1") (pintype "passive"))
      (node (ref "C4") (pin "1") (pinfunction "1_1") (pintype "passive"))
      (node (ref "C5") (pin "1") (pinfunction "1_1") (pintype "passive"))
      (node (ref "C6") (pin "1") (pinfunction "1_1") (pintype "passive"))
      (node (ref "C7") (pin "1") (pinfunction "1_1") (pintype "passive"))
      (node (ref "C9") (pin "1") (pinfunction "1_1") (pintype "passive"))
      (node (ref "D11") (pin "1") (pinfunction "A_1") (pintype "passive"))
      (node (ref "D4") (pin "1") (pinfunction "A_1") (pintype "passive"))
      (node (ref "D5") (pin "1") (pinfunction "A_1") (pintype "passive"))
      (node (ref "DPLC-L1") (pin "4") (pinfunction "GND_4") (pintype "passive"))
      (node (ref "J10") (pin "1") (pinfunction "1_1") (pintype "passive"))
      (node (ref "J3") (pin "1") (pinfunction "1_1") (pintype "passive"))
      (node (ref "J3") (pin "2") (pinfunction "2_2") (pintype "passive"))
      (node (ref "J3") (pin "3") (pinfunction "3_3") (pintype "passive"))
      (node (ref "J3") (pin "4") (pinfunction "4_4") (pintype "passive"))
      (node (ref "J4") (pin "1") (pinfunction "1_1") (pintype "passive"))
      (node (ref "J6") (pin "4") (pinfunction "4_4") (pintype "passive"))
      (node (ref "J9") (pin "6") (pinfunction "6_6") (pintype "passive"))
      (node (ref "Q1") (pin "2") (pinfunction "E_2") (pintype "passive"))
      (node (ref "Q2") (pin "2") (pinfunction "E_2") (pintype "passive"))
      (node (ref "Q3") (pin "2") (pinfunction "E_2") (pintype "passive"))
      (node (ref "Q4") (pin "2") (pinfunction "E_2") (pintype "passive"))
      (node (ref "R11") (pin "1") (pinfunction "1_1") (pintype "passive"))
      (node (ref "R12") (pin "1") (pinfunction "1_1") (pintype "passive"))
      (node (ref "R2") (pin "2") (pinfunction "2_2") (pintype "passive"))
      (node (ref "R25") (pin "1") (pinfunction "1_1") (pintype "passive"))
      (node (ref "R27") (pin "1") (pinfunction "1_1") (pintype "passive"))
      (node (ref "R28") (pin "1") (pinfunction "1_1") (pintype "passive"))
      (node (ref "R3") (pin "1") (pinfunction "1_1") (pintype "passive"))
      (node (ref "R30") (pin "1") (pinfunction "1_1") (pintype "passive"))
      (node (ref "R31") (pin "1") (pinfunction "1_1") (pintype "passive"))
      (node (ref "R32") (pin "2") (pinfunction "2_2") (pintype "passive"))
      (node (ref "RP3") (pin "5") (pinfunction "5_5") (pintype "passive"))
      (node (ref "RP4") (pin "1") (pinfunction "1_1") (pintype "passive"))
      (node (ref "RP4") (pin "2") (pinfunction "2_2") (pintype "passive"))
      (node (ref "RP4") (pin "3") (pinfunction "3_3") (pintype "passive"))
      (node (ref "RP4") (pin "4") (pinfunction "4_4") (pintype "passive"))
      (node (ref "S1") (pin "5") (pinfunction "5_5") (pintype "passive"))
      (node (ref "S1") (pin "6") (pinfunction "6_6") (pintype "passive"))
      (node (ref "S1") (pin "7") (pinfunction "7_7") (pintype "passive"))
      (node (ref "S1") (pin "8") (pinfunction "8_8") (pintype "passive"))
      (node (ref "S2") (pin "1") (pinfunction "COMMON_1") (pintype "passive"))
      (node (ref "U1") (pin "8") (pinfunction "GND_8") (pintype "power_in"))
      (node (ref "U2") (pin "8") (pinfunction "GND_8") (pintype "power_in"))
      (node (ref "U3") (pin "12") (pinfunction "VSSA_12") (pintype "power_in"))
      (node (ref "U3") (pin "18") (pinfunction "VSS_4_18") (pintype "power_in"))
      (node (ref "U3") (pin "31") (pinfunction "VSS_1_31") (pintype "power_in"))
      (node (ref "U3") (pin "47") (pinfunction "VSS_2_47") (pintype "power_in"))
      (node (ref "U3") (pin "63") (pinfunction "VSS_3_63") (pintype "power_in"))
      (node (ref "U4") (pin "2") (pinfunction "GND_2") (pintype "passive"))
      (node (ref "U4") (pin "8") (pinfunction "S_8") (pintype "passive"))
      (node (ref "U5") (pin "10") (pinfunction "N.C._10") (pintype "passive"))
      (node (ref "U5") (pin "11") (pinfunction "N.C._11") (pintype "passive"))
      (node (ref "U5") (pin "12") (pinfunction "N.C._12") (pintype "passive"))
      (node (ref "U5") (pin "13") (pinfunction "GND_13") (pintype "passive"))
      (node (ref "U5") (pin "5") (pinfunction "N.C._5") (pintype "passive"))
      (node (ref "U5") (pin "6") (pinfunction "N.C._6") (pintype "passive"))
      (node (ref "U5") (pin "7") (pinfunction "N.C._7") (pintype "passive"))
      (node (ref "U5") (pin "8") (pinfunction "N.C._8") (pintype "passive"))
      (node (ref "U5") (pin "9") (pinfunction "N.C._9") (pintype "passive"))
      (node (ref "U6") (pin "14") (pinfunction "AGND_14") (pintype "passive"))
      (node (ref "U6") (pin "16") (pinfunction "AGND_16") (pintype "passive"))
      (node (ref "U6") (pin "19") (pinfunction "AGND_19") (pintype "passive"))
      (node (ref "U6") (pin "29") (pinfunction "GND_29") (pintype "passive"))
      (node (ref "U6") (pin "3") (pinfunction "AGND_3") (pintype "passive"))
      (node (ref "U6") (pin "48") (pinfunction "AGND_48") (pintype "passive"))
      (node (ref "VR1") (pin "1") (pinfunction "GND_1") (pintype "passive"))
    )
    (net (code "56") (name "Net-(*1-GND)") (class "Default")
      (node (ref "*1") (pin "1") (pinfunction "GND_1") (pintype "passive"))
      (node (ref "D9") (pin "1") (pinfunction "A_1") (pintype "passive"))
      (node (ref "Q4") (pin "3") (pinfunction "C_3") (pintype "passive"))
    )
    (net (code "57") (name "Net-(*1-OFF)") (class "Default")
      (node (ref "*1") (pin "4") (pinfunction "OFF_4") (pintype "passive"))
      (node (ref "P1") (pin "1") (pinfunction "1_1") (pintype "passive"))
    )
    (net (code "58") (name "Net-(*1-ON)") (class "Default")
      (node (ref "*1") (pin "5") (pinfunction "ON_5") (pintype "passive"))
      (node (ref "J11") (pin "1") (pinfunction "GND_1") (pintype "passive"))
    )
    (net (code "59") (name "Net-(*2-BST)") (class "Default")
      (node (ref "*2") (pin "8") (pinfunction "BST_8") (pintype "passive"))
      (node (ref "C12") (pin "1") (pinfunction "1_1") (pintype "passive"))
    )
    (net (code "60") (name "Net-(*2-COMP)") (class "Default")
      (node (ref "*2") (pin "3") (pinfunction "COMP_3") (pintype "passive"))
      (node (ref "C20") (pin "2") (pinfunction "2_2") (pintype "passive"))
    )
    (net (code "61") (name "Net-(*2-EN)") (class "Default")
      (node (ref "*2") (pin "2") (pinfunction "EN_2") (pintype "passive"))
      (node (ref "J13") (pin "2") (pinfunction "2_2") (pintype "passive"))
      (node (ref "R24") (pin "1") (pinfunction "1_1") (pintype "passive"))
      (node (ref "R27") (pin "2") (pinfunction "2_2") (pintype "passive"))
    )
    (net (code "62") (name "Net-(*2-FB)") (class "Default")
      (node (ref "*2") (pin "4") (pinfunction "FB_4") (pintype "passive"))
      (node (ref "R29") (pin "1") (pinfunction "1_1") (pintype "passive"))
      (node (ref "R31") (pin "2") (pinfunction "2_2") (pintype "passive"))
    )
    (net (code "63") (name "Net-(*2-FREQ)") (class "Default")
      (node (ref "*2") (pin "6") (pinfunction "FREQ_6") (pintype "passive"))
      (node (ref "R28") (pin "2") (pinfunction "2_2") (pintype "passive"))
    )
    (net (code "64") (name "Net-(*2-SW)") (class "Default")
      (node (ref "*2") (pin "1") (pinfunction "SW_1") (pintype "passive"))
      (node (ref "C12") (pin "2") (pinfunction "2_2") (pintype "passive"))
      (node (ref "D11") (pin "2") (pinfunction "K_2") (pintype "passive"))
      (node (ref "L1") (pin "1") (pinfunction "1_1") (pintype "passive"))
    )
    (net (code "65") (name "Net-(C20-Pad1)") (class "Default")
      (node (ref "C20") (pin "1") (pinfunction "1_1") (pintype "passive"))
      (node (ref "R30") (pin "2") (pinfunction "2_2") (pintype "passive"))
    )
    (net (code "66") (name "Net-(D1-A)") (class "Default")
      (node (ref "D1") (pin "1") (pinfunction "A_1") (pintype "passive"))
      (node (ref "D4") (pin "2") (pinfunction "K_2") (pintype "passive"))
      (node (ref "W2") (pin "3") (pinfunction "3_3") (pintype "passive"))
    )
    (net (code "67") (name "Net-(D2-A)") (class "Default")
      (node (ref "D2") (pin "1") (pinfunction "A_1") (pintype "passive"))
      (node (ref "D5") (pin "2") (pinfunction "K_2") (pintype "passive"))
      (node (ref "W2") (pin "4") (pinfunction "4_4") (pintype "passive"))
    )
    (net (code "68") (name "Net-(D3-A)") (class "Default")
      (node (ref "D3") (pin "1") (pinfunction "A_1") (pintype "passive"))
      (node (ref "R5") (pin "2") (pinfunction "2_2") (pintype "passive"))
    )
    (net (code "69") (name "Net-(D7-PadK)") (class "Default")
      (node (ref "D7") (pin "K") (pinfunction "K_K") (pintype "passive"))
      (node (ref "R11") (pin "2") (pinfunction "2_2") (pintype "passive"))
    )
    (net (code "70") (name "Net-(D8-PadK)") (class "Default")
      (node (ref "D8") (pin "K") (pinfunction "K_K") (pintype "passive"))
      (node (ref "R12") (pin "2") (pinfunction "2_2") (pintype "passive"))
    )
    (net (code "71") (name "Net-(DPLC-L1-DC+)") (class "Default")
      (node (ref "DPLC-L1") (pin "7") (pinfunction "DC+_7") (pintype "passive"))
      (node (ref "W1") (pin "1") (pinfunction "1_1") (pintype "passive"))
    )
    (net (code "72") (name "Net-(DPLC-L1-DC-)") (class "Default")
      (node (ref "DPLC-L1") (pin "6") (pinfunction "DC-_6") (pintype "passive"))
      (node (ref "W1") (pin "2") (pinfunction "2_2") (pintype "passive"))
    )
    (net (code "73") (name "Net-(J12-CHS)") (class "Default")
      (node (ref "C15") (pin "2") (pinfunction "2_2") (pintype "passive"))
      (node (ref "C16") (pin "2") (pinfunction "2_2") (pintype "passive"))
      (node (ref "J12") (pin "13") (pinfunction "SHILD_13") (pintype "passive"))
      (node (ref "J12") (pin "14") (pinfunction "SHILD_14") (pintype "passive"))
      (node (ref "J12") (pin "8") (pinfunction "CHS_8") (pintype "passive"))
    )
    (net (code "74") (name "Net-(J12-D1-)") (class "Default")
      (node (ref "J12") (pin "10") (pinfunction "D1-_10") (pintype "passive"))
      (node (ref "R23") (pin "2") (pinfunction "2_2") (pintype "passive"))
    )
    (net (code "75") (name "Net-(J12-D2-)") (class "Default")
      (node (ref "J12") (pin "11") (pinfunction "D2-_11") (pintype "passive"))
      (node (ref "R26") (pin "2") (pinfunction "2_2") (pintype "passive"))
    )
    (net (code "76") (name "Net-(J12-RCT)") (class "Default")
      (node (ref "C19") (pin "2") (pinfunction "2_2") (pintype "passive"))
      (node (ref "J12") (pin "5") (pinfunction "RCT_5") (pintype "passive"))
      (node (ref "R21") (pin "1") (pinfunction "1_1") (pintype "passive"))
      (node (ref "R22") (pin "1") (pinfunction "1_1") (pintype "passive"))
    )
    (net (code "77") (name "Net-(J12-RDN)") (class "Default")
      (node (ref "C11") (pin "2") (pinfunction "2_2") (pintype "passive"))
      (node (ref "J12") (pin "6") (pinfunction "RDN_6") (pintype "passive"))
    )
    (net (code "78") (name "Net-(J12-RDP)") (class "Default")
      (node (ref "C8") (pin "2") (pinfunction "2_2") (pintype "passive"))
      (node (ref "J12") (pin "3") (pinfunction "RDP_3") (pintype "passive"))
    )
    (net (code "79") (name "Net-(J12-TCT)") (class "Default")
      (node (ref "C9") (pin "2") (pinfunction "2_2") (pintype "passive"))
      (node (ref "J12") (pin "4") (pinfunction "TCT_4") (pintype "passive"))
      (node (ref "R17") (pin "1") (pinfunction "1_1") (pintype "passive"))
    )
    (net (code "80") (name "Net-(Q1-B)") (class "Default")
      (node (ref "Q1") (pin "1") (pinfunction "B_1") (pintype "passive"))
      (node (ref "R6") (pin "2") (pinfunction "2_2") (pintype "passive"))
    )
    (net (code "81") (name "Net-(Q1-C)") (class "Default")
      (node (ref "J7") (pin "2") (pinfunction "2_2") (pintype "passive"))
      (node (ref "Q1") (pin "3") (pinfunction "C_3") (pintype "passive"))
    )
    (net (code "82") (name "Net-(Q2-B)") (class "Default")
      (node (ref "Q2") (pin "1") (pinfunction "B_1") (pintype "passive"))
      (node (ref "R7") (pin "2") (pinfunction "2_2") (pintype "passive"))
    )
    (net (code "83") (name "Net-(Q2-C)") (class "Default")
      (node (ref "J8") (pin "2") (pinfunction "2_2") (pintype "passive"))
      (node (ref "Q2") (pin "3") (pinfunction "C_3") (pintype "passive"))
    )
    (net (code "84") (name "Net-(Q3-B)") (class "Default")
      (node (ref "Q3") (pin "1") (pinfunction "B_1") (pintype "passive"))
      (node (ref "R8") (pin "2") (pinfunction "2_2") (pintype "passive"))
    )
    (net (code "85") (name "Net-(Q3-C)") (class "Default")
      (node (ref "Q3") (pin "3") (pinfunction "C_3") (pintype "passive"))
      (node (ref "w3") (pin "2") (pintype "passive"))
    )
    (net (code "86") (name "Net-(Q4-B)") (class "Default")
      (node (ref "Q4") (pin "1") (pinfunction "B_1") (pintype "passive"))
      (node (ref "R13") (pin "2") (pinfunction "2_2") (pintype "passive"))
    )
    (net (code "87") (name "Net-(R32-Pad1)") (class "Default")
      (node (ref "R32") (pin "1") (pinfunction "1_1") (pintype "passive"))
      (node (ref "U6") (pin "23") (pinfunction "RSVD_23") (pintype "passive"))
    )
    (net (code "88") (name "Net-(RP3-Pad4)") (class "Default")
      (node (ref "RP3") (pin "4") (pinfunction "4_4") (pintype "passive"))
      (node (ref "U6") (pin "42") (pinfunction "RSVD_42") (pintype "passive"))
    )
    (net (code "89") (name "Net-(RP4-Pad5)") (class "Default")
      (node (ref "RP4") (pin "5") (pinfunction "5_5") (pintype "passive"))
      (node (ref "U6") (pin "41") (pinfunction "RSVD_41") (pintype "passive"))
    )
    (net (code "90") (name "Net-(RP4-Pad6)") (class "Default")
      (node (ref "RP4") (pin "6") (pinfunction "6_6") (pintype "passive"))
      (node (ref "U6") (pin "40") (pinfunction "RSVD_40") (pintype "passive"))
    )
    (net (code "91") (name "Net-(RP4-Pad7)") (class "Default")
      (node (ref "RP4") (pin "7") (pinfunction "7_7") (pintype "passive"))
      (node (ref "U6") (pin "39") (pinfunction "RSVD_39") (pintype "passive"))
    )
    (net (code "92") (name "Net-(RP4-Pad8)") (class "Default")
      (node (ref "RP4") (pin "8") (pinfunction "8_8") (pintype "passive"))
      (node (ref "U6") (pin "38") (pinfunction "RSVD_38") (pintype "passive"))
    )
    (net (code "93") (name "Net-(S2-NO)") (class "Default")
      (node (ref "C5") (pin "2") (pinfunction "2_2") (pintype "passive"))
      (node (ref "R4") (pin "2") (pinfunction "2_2") (pintype "passive"))
      (node (ref "S2") (pin "2") (pinfunction "NO_2") (pintype "passive"))
      (node (ref "U3") (pin "7") (pinfunction "NRST_7") (pintype "bidirectional"))
    )
    (net (code "94") (name "Net-(U1-OUT1)") (class "Default")
      (node (ref "J1") (pin "1") (pinfunction "1_1") (pintype "passive"))
      (node (ref "U1") (pin "16") (pinfunction "OUT1_16") (pintype "open_collector"))
    )
    (net (code "95") (name "Net-(U1-OUT2)") (class "Default")
      (node (ref "J1") (pin "2") (pinfunction "2_2") (pintype "passive"))
      (node (ref "U1") (pin "15") (pinfunction "OUT2_15") (pintype "open_collector"))
    )
    (net (code "96") (name "Net-(U1-OUT3)") (class "Default")
      (node (ref "J1") (pin "3") (pinfunction "3_3") (pintype "passive"))
      (node (ref "U1") (pin "14") (pinfunction "OUT3_14") (pintype "open_collector"))
    )
    (net (code "97") (name "Net-(U1-OUT4)") (class "Default")
      (node (ref "J1") (pin "4") (pinfunction "4_4") (pintype "passive"))
      (node (ref "U1") (pin "13") (pinfunction "OUT4_13") (pintype "open_collector"))
    )
    (net (code "98") (name "Net-(U2-OUT1)") (class "Default")
      (node (ref "J2") (pin "1") (pinfunction "1_1") (pintype "passive"))
      (node (ref "U2") (pin "16") (pinfunction "OUT1_16") (pintype "open_collector"))
    )
    (net (code "99") (name "Net-(U2-OUT2)") (class "Default")
      (node (ref "J2") (pin "2") (pinfunction "2_2") (pintype "passive"))
      (node (ref "U2") (pin "15") (pinfunction "OUT2_15") (pintype "open_collector"))
    )
    (net (code "100") (name "Net-(U2-OUT3)") (class "Default")
      (node (ref "J2") (pin "3") (pinfunction "3_3") (pintype "passive"))
      (node (ref "U2") (pin "14") (pinfunction "OUT3_14") (pintype "open_collector"))
    )
    (net (code "101") (name "Net-(U2-OUT4)") (class "Default")
      (node (ref "J2") (pin "4") (pinfunction "4_4") (pintype "passive"))
      (node (ref "U2") (pin "13") (pinfunction "OUT4_13") (pintype "open_collector"))
    )
    (net (code "102") (name "Net-(U3-BOOT0)") (class "Default")
      (node (ref "R3") (pin "2") (pinfunction "2_2") (pintype "passive"))
      (node (ref "U3") (pin "60") (pinfunction "BOOT0_60") (pintype "input"))
    )
    (net (code "103") (name "Net-(U3-OSC_IN{slash}PD0)") (class "Default")
      (node (ref "C3") (pin "2") (pinfunction "2_2") (pintype "passive"))
      (node (ref "U3") (pin "5") (pinfunction "OSC_IN/PD0_5") (pintype "input"))
      (node (ref "Y1") (pin "2") (pinfunction "OSC2_2") (pintype "passive"))
    )
    (net (code "104") (name "Net-(U3-OSC_OUT{slash}PD1)") (class "Default")
      (node (ref "C4") (pin "2") (pinfunction "2_2") (pintype "passive"))
      (node (ref "U3") (pin "6") (pinfunction "OSC_OUT/PD1_6") (pintype "output"))
      (node (ref "Y1") (pin "1") (pinfunction "OSC1_1") (pintype "passive"))
    )
    (net (code "105") (name "Net-(U3-PB2{slash}BOOT1)") (class "Default")
      (node (ref "R2") (pin "1") (pinfunction "1_1") (pintype "passive"))
      (node (ref "U3") (pin "28") (pinfunction "PB2/BOOT1_28") (pintype "bidirectional"))
    )
    (net (code "106") (name "Net-(U3-PC0)") (class "Default")
      (node (ref "RP1") (pin "8") (pinfunction "8_8") (pintype "passive"))
      (node (ref "S1") (pin "1") (pinfunction "1_1") (pintype "passive"))
      (node (ref "U3") (pin "8") (pinfunction "PC0_8") (pintype "bidirectional"))
    )
    (net (code "107") (name "Net-(U3-PC1)") (class "Default")
      (node (ref "RP1") (pin "7") (pinfunction "7_7") (pintype "passive"))
      (node (ref "S1") (pin "2") (pinfunction "2_2") (pintype "passive"))
      (node (ref "U3") (pin "9") (pinfunction "PC1_9") (pintype "bidirectional"))
    )
    (net (code "108") (name "Net-(U3-PC2)") (class "Default")
      (node (ref "RP1") (pin "6") (pinfunction "6_6") (pintype "passive"))
      (node (ref "S1") (pin "3") (pinfunction "3_3") (pintype "passive"))
      (node (ref "U3") (pin "10") (pinfunction "PC2_10") (pintype "bidirectional"))
    )
    (net (code "109") (name "Net-(U3-PC3)") (class "Default")
      (node (ref "RP1") (pin "5") (pinfunction "5_5") (pintype "passive"))
      (node (ref "S1") (pin "4") (pinfunction "4_4") (pintype "passive"))
      (node (ref "U3") (pin "11") (pinfunction "PC3_11") (pintype "bidirectional"))
    )
    (net (code "110") (name "Net-(U4-CANH)") (class "Default")
      (node (ref "J5") (pin "2") (pinfunction "2_2") (pintype "passive"))
      (node (ref "R1") (pin "1") (pinfunction "1_1") (pintype "passive"))
      (node (ref "U4") (pin "7") (pinfunction "CANH_7") (pintype "passive"))
    )
    (net (code "111") (name "Net-(U4-CANL)") (class "Default")
      (node (ref "J5") (pin "1") (pinfunction "1_1") (pintype "passive"))
      (node (ref "R1") (pin "2") (pinfunction "2_2") (pintype "passive"))
      (node (ref "U4") (pin "6") (pinfunction "CANL_6") (pintype "passive"))
    )
    (net (code "112") (name "Net-(U6-1V2O)") (class "Default")
      (node (ref "C26") (pin "1") (pinfunction "1_1") (pintype "passive"))
      (node (ref "U6") (pin "22") (pinfunction "1V2O_22") (pintype "passive"))
    )
    (net (code "113") (name "Net-(U6-EXRES1)") (class "Default")
      (node (ref "R25") (pin "2") (pinfunction "2_2") (pintype "passive"))
      (node (ref "U6") (pin "10") (pinfunction "EXRES1_10") (pintype "passive"))
    )
    (net (code "114") (name "Net-(U6-TOCAP)") (class "Default")
      (node (ref "C27") (pin "1") (pinfunction "1_1") (pintype "passive"))
      (node (ref "U6") (pin "20") (pinfunction "TOCAP_20") (pintype "passive"))
    )
    (net (code "115") (name "Net-(U6-XI{slash}CLCKIN)") (class "Default")
      (node (ref "C13") (pin "1") (pinfunction "1_1") (pintype "passive"))
      (node (ref "R20") (pin "1") (pinfunction "1_1") (pintype "passive"))
      (node (ref "U6") (pin "30") (pinfunction "XI/CLCKIN_30") (pintype "passive"))
      (node (ref "Y2") (pin "1") (pinfunction "OSC1_1") (pintype "passive"))
    )
    (net (code "116") (name "Net-(U6-XO)") (class "Default")
      (node (ref "C10") (pin "1") (pinfunction "1_1") (pintype "passive"))
      (node (ref "R20") (pin "2") (pinfunction "2_2") (pintype "passive"))
      (node (ref "U6") (pin "31") (pinfunction "XO_31") (pintype "passive"))
      (node (ref "Y2") (pin "3") (pinfunction "OSC2_3") (pintype "passive"))
    )
    (net (code "117") (name "unconnected-(DPLC-L1-Pad5)") (class "Default")
      (node (ref "DPLC-L1") (pin "5") (pinfunction "5_5") (pintype "passive"))
    )
    (net (code "118") (name "unconnected-(J12-NC-Pad7)") (class "Default")
      (node (ref "J12") (pin "7") (pinfunction "NC_7") (pintype "passive"))
    )
    (net (code "119") (name "unconnected-(R29-Pad2)") (class "Default")
      (node (ref "R29") (pin "2") (pinfunction "2_2") (pintype "passive"))
    )
    (net (code "120") (name "unconnected-(U1-IN5-Pad5)") (class "Default")
      (node (ref "U1") (pin "5") (pinfunction "IN5_5") (pintype "input"))
    )
    (net (code "121") (name "unconnected-(U1-IN6-Pad6)") (class "Default")
      (node (ref "U1") (pin "6") (pinfunction "IN6_6") (pintype "input"))
    )
    (net (code "122") (name "unconnected-(U1-IN7-Pad7)") (class "Default")
      (node (ref "U1") (pin "7") (pinfunction "IN7_7") (pintype "input"))
    )
    (net (code "123") (name "unconnected-(U1-OUT5-Pad12)") (class "Default")
      (node (ref "U1") (pin "12") (pinfunction "OUT5_12") (pintype "open_collector"))
    )
    (net (code "124") (name "unconnected-(U1-OUT6-Pad11)") (class "Default")
      (node (ref "U1") (pin "11") (pinfunction "OUT6_11") (pintype "open_collector"))
    )
    (net (code "125") (name "unconnected-(U1-OUT7-Pad10)") (class "Default")
      (node (ref "U1") (pin "10") (pinfunction "OUT7_10") (pintype "open_collector"))
    )
    (net (code "126") (name "unconnected-(U2-IN5-Pad5)") (class "Default")
      (node (ref "U2") (pin "5") (pinfunction "IN5_5") (pintype "input"))
    )
    (net (code "127") (name "unconnected-(U2-IN6-Pad6)") (class "Default")
      (node (ref "U2") (pin "6") (pinfunction "IN6_6") (pintype "input"))
    )
    (net (code "128") (name "unconnected-(U2-IN7-Pad7)") (class "Default")
      (node (ref "U2") (pin "7") (pinfunction "IN7_7") (pintype "input"))
    )
    (net (code "129") (name "unconnected-(U2-OUT5-Pad12)") (class "Default")
      (node (ref "U2") (pin "12") (pinfunction "OUT5_12") (pintype "open_collector"))
    )
    (net (code "130") (name "unconnected-(U2-OUT6-Pad11)") (class "Default")
      (node (ref "U2") (pin "11") (pinfunction "OUT6_11") (pintype "open_collector"))
    )
    (net (code "131") (name "unconnected-(U2-OUT7-Pad10)") (class "Default")
      (node (ref "U2") (pin "10") (pinfunction "OUT7_10") (pintype "open_collector"))
    )
    (net (code "132") (name "unconnected-(U3-PA0-WKUP-Pad14)") (class "Default")
      (node (ref "U3") (pin "14") (pinfunction "PA0-WKUP_14") (pintype "bidirectional"))
    )
    (net (code "133") (name "unconnected-(U3-PA15{slash}JTDI-Pad50)") (class "Default")
      (node (ref "U3") (pin "50") (pinfunction "PA15/JTDI_50") (pintype "bidirectional"))
    )
    (net (code "134") (name "unconnected-(U3-PB3{slash}JTDO-Pad55)") (class "Default")
      (node (ref "U3") (pin "55") (pinfunction "PB3/JTDO_55") (pintype "bidirectional"))
    )
    (net (code "135") (name "unconnected-(U3-PC13-TAMPER-RTC-Pad2)") (class "Default")
      (node (ref "U3") (pin "2") (pinfunction "PC13-TAMPER-RTC_2") (pintype "bidirectional"))
    )
    (net (code "136") (name "unconnected-(U3-PC14-OSC32_IN-Pad3)") (class "Default")
      (node (ref "U3") (pin "3") (pinfunction "PC14-OSC32_IN_3") (pintype "bidirectional"))
    )
    (net (code "137") (name "unconnected-(U3-PC15-OSC32_OUT-Pad4)") (class "Default")
      (node (ref "U3") (pin "4") (pinfunction "PC15-OSC32_OUT_4") (pintype "bidirectional"))
    )
    (net (code "138") (name "unconnected-(U3-PD2-Pad54)") (class "Default")
      (node (ref "U3") (pin "54") (pinfunction "PD2_54") (pintype "bidirectional"))
    )
    (net (code "139") (name "unconnected-(U4-n.c.-Pad5)") (class "Default")
      (node (ref "U4") (pin "5") (pinfunction "n.c._5") (pintype "passive"))
    )
    (net (code "140") (name "unconnected-(U5-~{RST}-Pad4)") (class "Default")
      (node (ref "U5") (pin "4") (pinfunction "~{RST}_4") (pintype "passive"))
    )
    (net (code "141") (name "unconnected-(U6-AGND-Pad9)") (class "Default")
      (node (ref "U6") (pin "9") (pinfunction "AGND_9") (pintype "passive"))
    )
    (net (code "142") (name "unconnected-(U6-AVDD-Pad8)") (class "Default")
      (node (ref "U6") (pin "8") (pinfunction "AVDD_8") (pintype "passive"))
    )
    (net (code "143") (name "unconnected-(U6-AVDD-Pad11)") (class "Default")
      (node (ref "U6") (pin "11") (pinfunction "AVDD_11") (pintype "passive"))
    )
    (net (code "144") (name "unconnected-(U6-DNC-Pad7)") (class "Default")
      (node (ref "U6") (pin "7") (pinfunction "DNC_7") (pintype "passive"))
    )
    (net (code "145") (name "unconnected-(U6-DUPLED-Pad26)") (class "Default")
      (node (ref "U6") (pin "26") (pinfunction "DUPLED_26") (pintype "passive"))
    )
    (net (code "146") (name "unconnected-(U6-NC-Pad12)") (class "Default")
      (node (ref "U6") (pin "12") (pinfunction "NC_12") (pintype "passive"))
    )
    (net (code "147") (name "unconnected-(U6-NC-Pad13)") (class "Default")
      (node (ref "U6") (pin "13") (pinfunction "NC_13") (pintype "passive"))
    )
    (net (code "148") (name "unconnected-(U6-NC-Pad46)") (class "Default")
      (node (ref "U6") (pin "46") (pinfunction "NC_46") (pintype "passive"))
    )
    (net (code "149") (name "unconnected-(U6-NC-Pad47)") (class "Default")
      (node (ref "U6") (pin "47") (pinfunction "NC_47") (pintype "passive"))
    )
    (net (code "150") (name "unconnected-(U6-SPDLED-Pad24)") (class "Default")
      (node (ref "U6") (pin "24") (pinfunction "SPDLED_24") (pintype "passive+no_connect"))
    )
    (net (code "151") (name "unconnected-(U6-VBG-Pad18)") (class "Default")
      (node (ref "U6") (pin "18") (pinfunction "VBG_18") (pintype "passive"))
    )
  )
)
